# esp32.net
KiCad netlist of a schematic drawn in Altium Designer
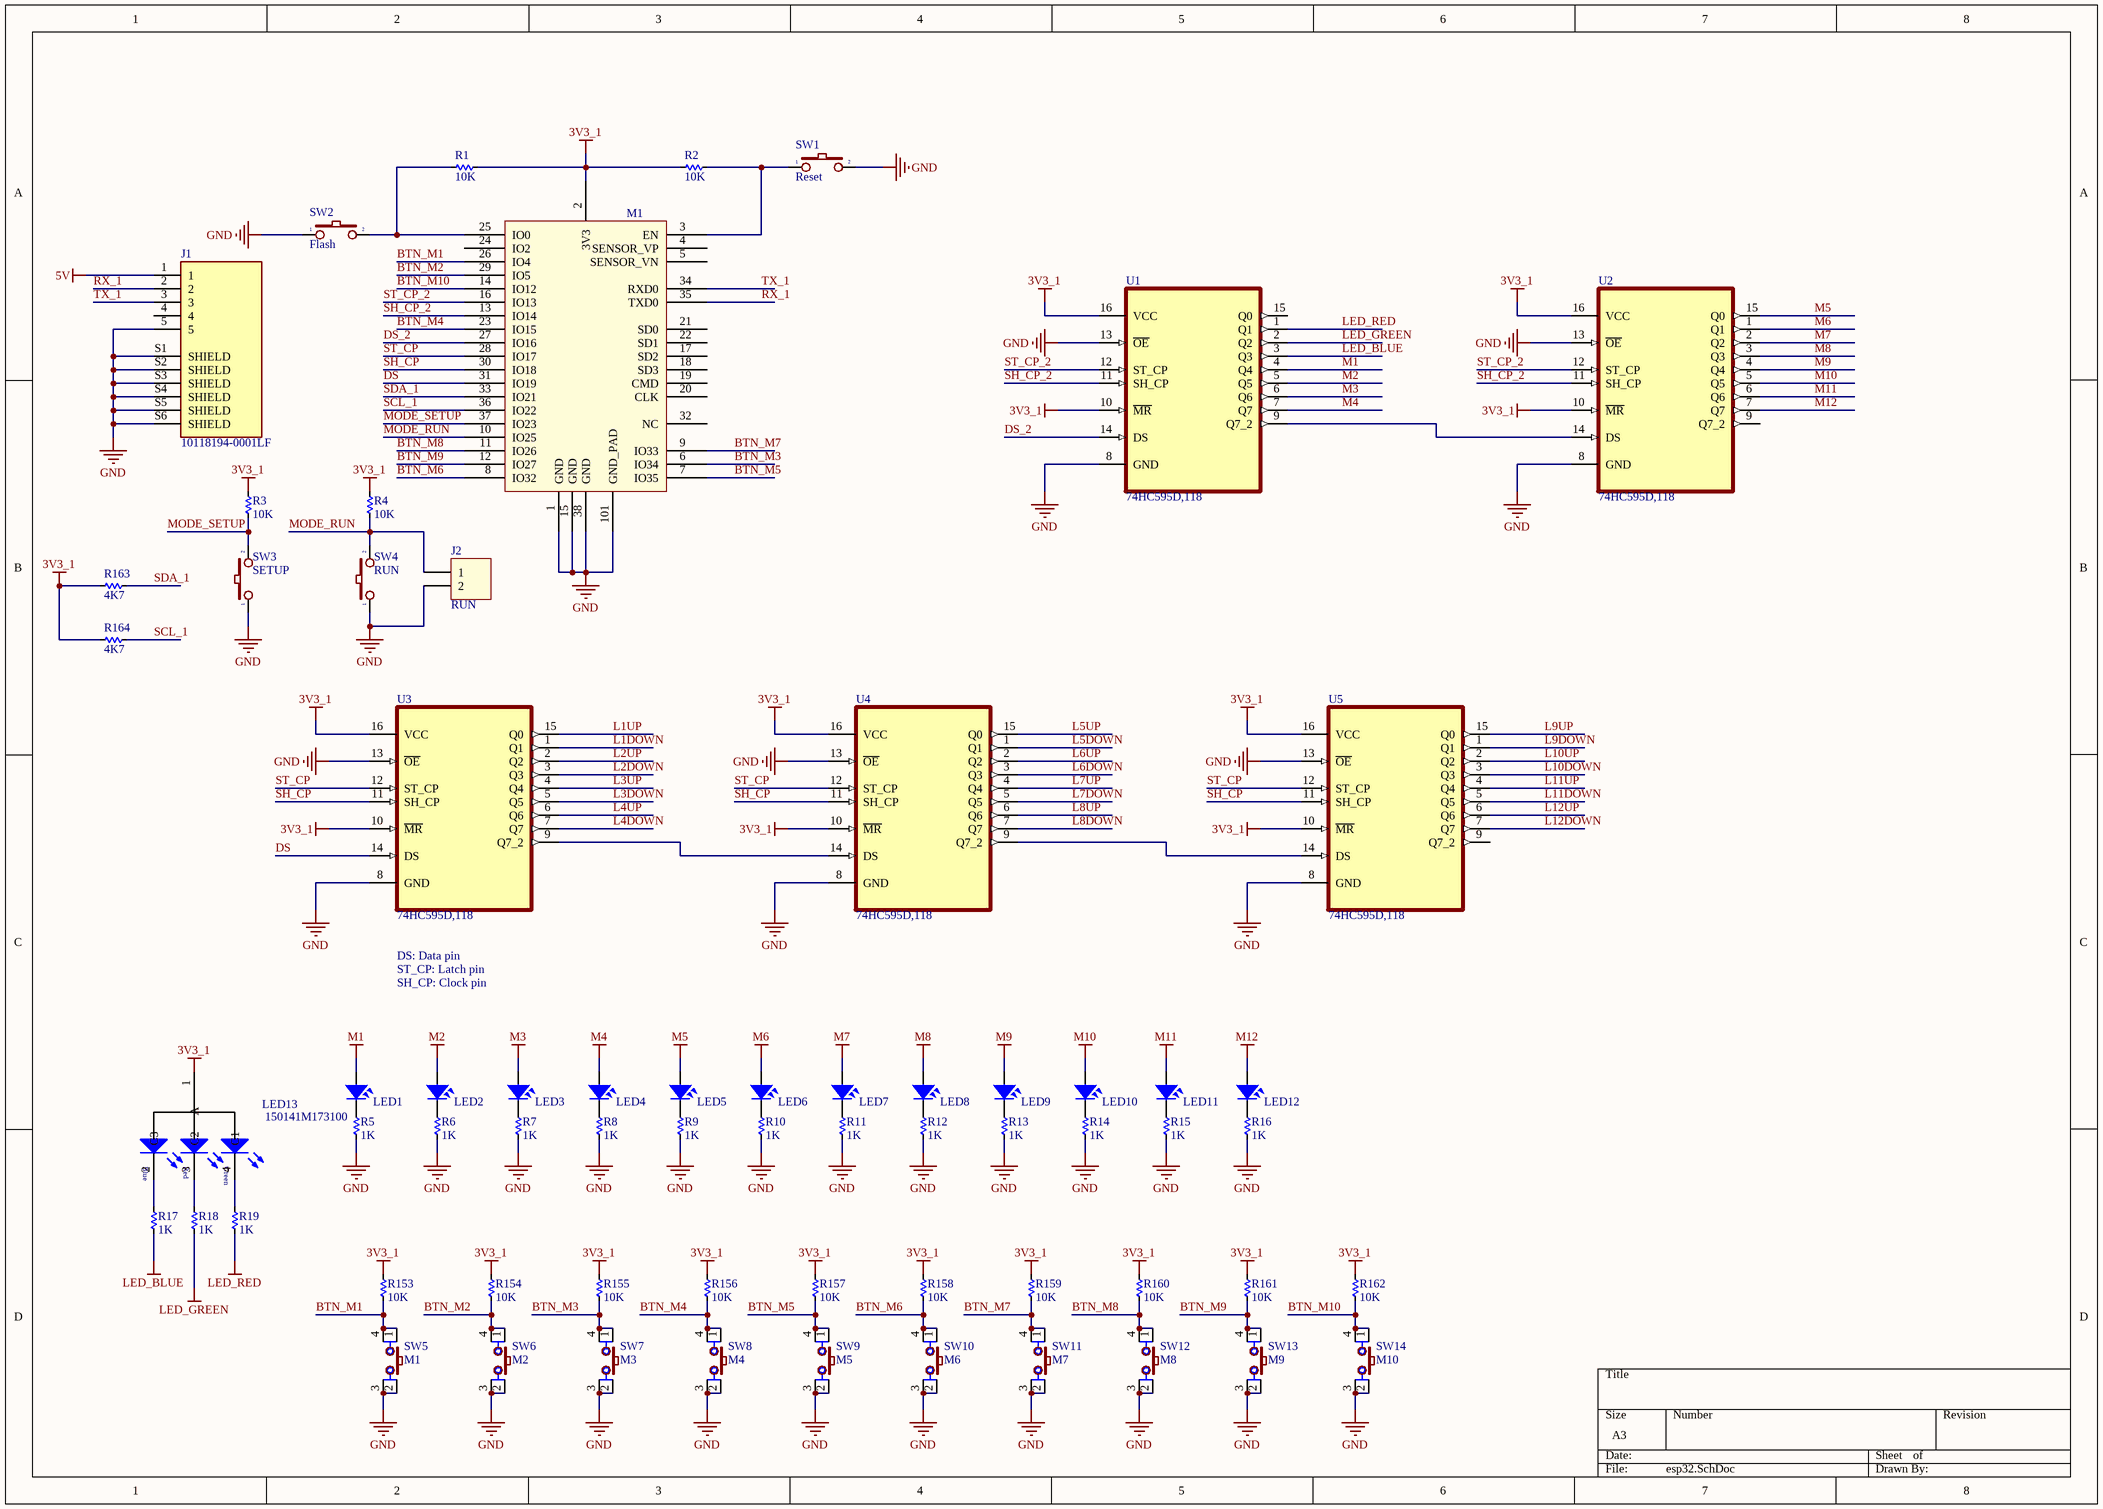
[diagram p0: esp32.SchDoc]

(export (version "E")
  (design (tool "Eeschema 10.0.6"))
  (components
    (comp (ref "J1")
      (value "10118194-0001LF")
      (footprint "AMPHENOL_10118194-0001LF")
      (description "USB - micro B USB 2.0 Receptacle Connector 5 Position Surface Mount, Right Angle; Through Hole")
      (fields (field (name "MF") "Amphenol ICC"))
      (libsource (lib "10118194-0001LF") (part "10118194-0001LF"))
    )
    (comp (ref "J2")
      (value "RUN")
      (footprint "62000211622")
      (description "WR-WTB 2.00mm Male Vertical Shrouded Header, 2p")
      (fields (field (name "PART NUMBER") "62000211622") (field (name "PUBLISHER") "Wurth Elektronik"))
      (libsource (lib "Header2.0") (part "62000211622"))
    )
    (comp (ref "LED1") (value "LED") (footprint "LED-0805-Blue") (libsource (lib "LIBRARY") (part "LED SMD")))
    (comp (ref "LED2") (value "LED") (footprint "LED-0805-Blue") (libsource (lib "LIBRARY") (part "LED SMD")))
    (comp (ref "LED3") (value "LED") (footprint "LED-0805-Blue") (libsource (lib "LIBRARY") (part "LED SMD")))
    (comp (ref "LED4") (value "LED") (footprint "LED-0805-Blue") (libsource (lib "LIBRARY") (part "LED SMD")))
    (comp (ref "LED5") (value "LED") (footprint "LED-0805-Blue") (libsource (lib "LIBRARY") (part "LED SMD")))
    (comp (ref "LED6") (value "LED") (footprint "LED-0805-Blue") (libsource (lib "LIBRARY") (part "LED SMD")))
    (comp (ref "LED7") (value "LED") (footprint "LED-0805-Blue") (libsource (lib "LIBRARY") (part "LED SMD")))
    (comp (ref "LED8") (value "LED") (footprint "LED-0805-Blue") (libsource (lib "LIBRARY") (part "LED SMD")))
    (comp (ref "LED9") (value "LED") (footprint "LED-0805-Blue") (libsource (lib "LIBRARY") (part "LED SMD")))
    (comp (ref "LED10")
      (value "LED")
      (footprint "LED-0805-Blue")
      (libsource (lib "LIBRARY") (part "LED SMD"))
    )
    (comp (ref "LED11")
      (value "LED")
      (footprint "LED-0805-Blue")
      (libsource (lib "LIBRARY") (part "LED SMD"))
    )
    (comp (ref "LED12")
      (value "LED")
      (footprint "LED-0805-Blue")
      (libsource (lib "LIBRARY") (part "LED SMD"))
    )
    (comp (ref "LED13")
      (value "150141M173100")
      (footprint "LED RGB 3528")
      (description "SMD Full-Color Top LED, WL-SFTW, Red & Green & Blue")
      (fields
        (field (name "MANUFACTURER") "Würth Elektronik eiSos GmbH")
        (field (name "CREATED BY") "Christin Otto")
      )
      (libsource (lib "LIBRARY") (part "LED RGB SMD"))
    )
    (comp (ref "M1")
      (value "ESP32S_Module")
      (footprint "ESP32S")
      (description "Esp-32S")
      (libsource (lib "ESP32S") (part "ESP32S_Module"))
    )
    (comp (ref "R1")
      (value "10K")
      (footprint "RES-SMD-0805")
      (description "Resistor")
      (fields
        (field (name "MANUFACTURER") "Generic Components")
        (field (name "PUBLISHER") "Altium Hobart Technology Centre")
      )
      (libsource (lib "LIBRARY") (part "Res-SMD"))
    )
    (comp (ref "R2")
      (value "10K")
      (footprint "RES-SMD-0805")
      (description "Resistor")
      (fields
        (field (name "MANUFACTURER") "Generic Components")
        (field (name "PUBLISHER") "Altium Hobart Technology Centre")
      )
      (libsource (lib "LIBRARY") (part "Res-SMD"))
    )
    (comp (ref "R3")
      (value "10K")
      (footprint "RES-SMD-0805")
      (description "Resistor")
      (fields
        (field (name "MANUFACTURER") "Generic Components")
        (field (name "PUBLISHER") "Altium Hobart Technology Centre")
      )
      (libsource (lib "LIBRARY") (part "Res-SMD"))
    )
    (comp (ref "R4")
      (value "10K")
      (footprint "RES-SMD-0805")
      (description "Resistor")
      (fields
        (field (name "MANUFACTURER") "Generic Components")
        (field (name "PUBLISHER") "Altium Hobart Technology Centre")
      )
      (libsource (lib "LIBRARY") (part "Res-SMD"))
    )
    (comp (ref "R5")
      (value "1K")
      (footprint "RES-SMD-0805")
      (description "Resistor")
      (fields
        (field (name "MANUFACTURER") "Generic Components")
        (field (name "PUBLISHER") "Altium Hobart Technology Centre")
      )
      (libsource (lib "LIBRARY") (part "Res-SMD"))
    )
    (comp (ref "R6")
      (value "1K")
      (footprint "RES-SMD-0805")
      (description "Resistor")
      (fields
        (field (name "MANUFACTURER") "Generic Components")
        (field (name "PUBLISHER") "Altium Hobart Technology Centre")
      )
      (libsource (lib "LIBRARY") (part "Res-SMD"))
    )
    (comp (ref "R7")
      (value "1K")
      (footprint "RES-SMD-0805")
      (description "Resistor")
      (fields
        (field (name "MANUFACTURER") "Generic Components")
        (field (name "PUBLISHER") "Altium Hobart Technology Centre")
      )
      (libsource (lib "LIBRARY") (part "Res-SMD"))
    )
    (comp (ref "R8")
      (value "1K")
      (footprint "RES-SMD-0805")
      (description "Resistor")
      (fields
        (field (name "MANUFACTURER") "Generic Components")
        (field (name "PUBLISHER") "Altium Hobart Technology Centre")
      )
      (libsource (lib "LIBRARY") (part "Res-SMD"))
    )
    (comp (ref "R9")
      (value "1K")
      (footprint "RES-SMD-0805")
      (description "Resistor")
      (fields
        (field (name "MANUFACTURER") "Generic Components")
        (field (name "PUBLISHER") "Altium Hobart Technology Centre")
      )
      (libsource (lib "LIBRARY") (part "Res-SMD"))
    )
    (comp (ref "R10")
      (value "1K")
      (footprint "RES-SMD-0805")
      (description "Resistor")
      (fields
        (field (name "MANUFACTURER") "Generic Components")
        (field (name "PUBLISHER") "Altium Hobart Technology Centre")
      )
      (libsource (lib "LIBRARY") (part "Res-SMD"))
    )
    (comp (ref "R11")
      (value "1K")
      (footprint "RES-SMD-0805")
      (description "Resistor")
      (fields
        (field (name "MANUFACTURER") "Generic Components")
        (field (name "PUBLISHER") "Altium Hobart Technology Centre")
      )
      (libsource (lib "LIBRARY") (part "Res-SMD"))
    )
    (comp (ref "R12")
      (value "1K")
      (footprint "RES-SMD-0805")
      (description "Resistor")
      (fields
        (field (name "MANUFACTURER") "Generic Components")
        (field (name "PUBLISHER") "Altium Hobart Technology Centre")
      )
      (libsource (lib "LIBRARY") (part "Res-SMD"))
    )
    (comp (ref "R13")
      (value "1K")
      (footprint "RES-SMD-0805")
      (description "Resistor")
      (fields
        (field (name "MANUFACTURER") "Generic Components")
        (field (name "PUBLISHER") "Altium Hobart Technology Centre")
      )
      (libsource (lib "LIBRARY") (part "Res-SMD"))
    )
    (comp (ref "R14")
      (value "1K")
      (footprint "RES-SMD-0805")
      (description "Resistor")
      (fields
        (field (name "MANUFACTURER") "Generic Components")
        (field (name "PUBLISHER") "Altium Hobart Technology Centre")
      )
      (libsource (lib "LIBRARY") (part "Res-SMD"))
    )
    (comp (ref "R15")
      (value "1K")
      (footprint "RES-SMD-0805")
      (description "Resistor")
      (fields
        (field (name "MANUFACTURER") "Generic Components")
        (field (name "PUBLISHER") "Altium Hobart Technology Centre")
      )
      (libsource (lib "LIBRARY") (part "Res-SMD"))
    )
    (comp (ref "R16")
      (value "1K")
      (footprint "RES-SMD-0805")
      (description "Resistor")
      (fields
        (field (name "MANUFACTURER") "Generic Components")
        (field (name "PUBLISHER") "Altium Hobart Technology Centre")
      )
      (libsource (lib "LIBRARY") (part "Res-SMD"))
    )
    (comp (ref "R17")
      (value "1K")
      (footprint "RES-SMD-0805")
      (description "Resistor")
      (fields
        (field (name "MANUFACTURER") "Generic Components")
        (field (name "PUBLISHER") "Altium Hobart Technology Centre")
      )
      (libsource (lib "LIBRARY") (part "Res-SMD"))
    )
    (comp (ref "R18")
      (value "1K")
      (footprint "RES-SMD-0805")
      (description "Resistor")
      (fields
        (field (name "MANUFACTURER") "Generic Components")
        (field (name "PUBLISHER") "Altium Hobart Technology Centre")
      )
      (libsource (lib "LIBRARY") (part "Res-SMD"))
    )
    (comp (ref "R19")
      (value "1K")
      (footprint "RES-SMD-0805")
      (description "Resistor")
      (fields
        (field (name "MANUFACTURER") "Generic Components")
        (field (name "PUBLISHER") "Altium Hobart Technology Centre")
      )
      (libsource (lib "LIBRARY") (part "Res-SMD"))
    )
    (comp (ref "R153")
      (value "10K")
      (footprint "RES-SMD-0805")
      (description "Resistor")
      (fields
        (field (name "MANUFACTURER") "Generic Components")
        (field (name "PUBLISHER") "Altium Hobart Technology Centre")
      )
      (libsource (lib "LIBRARY") (part "Res-SMD"))
    )
    (comp (ref "R154")
      (value "10K")
      (footprint "RES-SMD-0805")
      (description "Resistor")
      (fields
        (field (name "MANUFACTURER") "Generic Components")
        (field (name "PUBLISHER") "Altium Hobart Technology Centre")
      )
      (libsource (lib "LIBRARY") (part "Res-SMD"))
    )
    (comp (ref "R155")
      (value "10K")
      (footprint "RES-SMD-0805")
      (description "Resistor")
      (fields
        (field (name "MANUFACTURER") "Generic Components")
        (field (name "PUBLISHER") "Altium Hobart Technology Centre")
      )
      (libsource (lib "LIBRARY") (part "Res-SMD"))
    )
    (comp (ref "R156")
      (value "10K")
      (footprint "RES-SMD-0805")
      (description "Resistor")
      (fields
        (field (name "MANUFACTURER") "Generic Components")
        (field (name "PUBLISHER") "Altium Hobart Technology Centre")
      )
      (libsource (lib "LIBRARY") (part "Res-SMD"))
    )
    (comp (ref "R157")
      (value "10K")
      (footprint "RES-SMD-0805")
      (description "Resistor")
      (fields
        (field (name "MANUFACTURER") "Generic Components")
        (field (name "PUBLISHER") "Altium Hobart Technology Centre")
      )
      (libsource (lib "LIBRARY") (part "Res-SMD"))
    )
    (comp (ref "R158")
      (value "10K")
      (footprint "RES-SMD-0805")
      (description "Resistor")
      (fields
        (field (name "MANUFACTURER") "Generic Components")
        (field (name "PUBLISHER") "Altium Hobart Technology Centre")
      )
      (libsource (lib "LIBRARY") (part "Res-SMD"))
    )
    (comp (ref "R159")
      (value "10K")
      (footprint "RES-SMD-0805")
      (description "Resistor")
      (fields
        (field (name "MANUFACTURER") "Generic Components")
        (field (name "PUBLISHER") "Altium Hobart Technology Centre")
      )
      (libsource (lib "LIBRARY") (part "Res-SMD"))
    )
    (comp (ref "R160")
      (value "10K")
      (footprint "RES-SMD-0805")
      (description "Resistor")
      (fields
        (field (name "MANUFACTURER") "Generic Components")
        (field (name "PUBLISHER") "Altium Hobart Technology Centre")
      )
      (libsource (lib "LIBRARY") (part "Res-SMD"))
    )
    (comp (ref "R161")
      (value "10K")
      (footprint "RES-SMD-0805")
      (description "Resistor")
      (fields
        (field (name "MANUFACTURER") "Generic Components")
        (field (name "PUBLISHER") "Altium Hobart Technology Centre")
      )
      (libsource (lib "LIBRARY") (part "Res-SMD"))
    )
    (comp (ref "R162")
      (value "10K")
      (footprint "RES-SMD-0805")
      (description "Resistor")
      (fields
        (field (name "MANUFACTURER") "Generic Components")
        (field (name "PUBLISHER") "Altium Hobart Technology Centre")
      )
      (libsource (lib "LIBRARY") (part "Res-SMD"))
    )
    (comp (ref "R163")
      (value "4K7")
      (footprint "RES-SMD-0805")
      (description "Resistor")
      (fields
        (field (name "MANUFACTURER") "Generic Components")
        (field (name "PUBLISHER") "Altium Hobart Technology Centre")
      )
      (libsource (lib "LIBRARY") (part "Res-SMD"))
    )
    (comp (ref "R164")
      (value "4K7")
      (footprint "RES-SMD-0805")
      (description "Resistor")
      (fields
        (field (name "MANUFACTURER") "Generic Components")
        (field (name "PUBLISHER") "Altium Hobart Technology Centre")
      )
      (libsource (lib "LIBRARY") (part "Res-SMD"))
    )
    (comp (ref "SW1")
      (value "Reset")
      (footprint "SW1-SMD")
      (description "Switch button 2 pin")
      (libsource (lib "LIBRARY") (part "SW2"))
    )
    (comp (ref "SW2")
      (value "Flash")
      (footprint "SW-DIP1-1")
      (description "Switch button 2 pin")
      (libsource (lib "LIBRARY") (part "SW2"))
    )
    (comp (ref "SW3")
      (value "SETUP")
      (footprint "SW-DIP1-1")
      (description "Switch button 2 pin")
      (libsource (lib "LIBRARY") (part "SW2"))
    )
    (comp (ref "SW4")
      (value "RUN")
      (footprint "SW-DIP1-1")
      (description "Switch button 2 pin")
      (libsource (lib "LIBRARY") (part "SW2"))
    )
    (comp (ref "SW5")
      (value "M1")
      (footprint "SW2-SMD")
      (description "Switch button 4 pin")
      (libsource (lib "LIBTanCN") (part "SW4"))
    )
    (comp (ref "SW6")
      (value "M2")
      (footprint "SW2-SMD")
      (description "Switch button 4 pin")
      (libsource (lib "LIBTanCN") (part "SW4"))
    )
    (comp (ref "SW7")
      (value "M3")
      (footprint "SW2-SMD")
      (description "Switch button 4 pin")
      (libsource (lib "LIBTanCN") (part "SW4"))
    )
    (comp (ref "SW8")
      (value "M4")
      (footprint "SW2-SMD")
      (description "Switch button 4 pin")
      (libsource (lib "LIBTanCN") (part "SW4"))
    )
    (comp (ref "SW9")
      (value "M5")
      (footprint "SW2-SMD")
      (description "Switch button 4 pin")
      (libsource (lib "LIBTanCN") (part "SW4"))
    )
    (comp (ref "SW10")
      (value "M6")
      (footprint "SW2-SMD")
      (description "Switch button 4 pin")
      (libsource (lib "LIBTanCN") (part "SW4"))
    )
    (comp (ref "SW11")
      (value "M7")
      (footprint "SW2-SMD")
      (description "Switch button 4 pin")
      (libsource (lib "LIBTanCN") (part "SW4"))
    )
    (comp (ref "SW12")
      (value "M8")
      (footprint "SW2-SMD")
      (description "Switch button 4 pin")
      (libsource (lib "LIBTanCN") (part "SW4"))
    )
    (comp (ref "SW13")
      (value "M9")
      (footprint "SW2-SMD")
      (description "Switch button 4 pin")
      (libsource (lib "LIBTanCN") (part "SW4"))
    )
    (comp (ref "SW14")
      (value "M10")
      (footprint "SW2-SMD")
      (description "Switch button 4 pin")
      (libsource (lib "LIBTanCN") (part "SW4"))
    )
    (comp (ref "U1")
      (value "74HC595D,118")
      (footprint "SOIC127P600X175-16N")
      (description "Shift Shift Register 1 Element 8 Bit 16-SO")
      (fields (field (name "MF") "Nexperia USA Inc."))
      (libsource (lib "74HC595D_118") (part "74HC595D,118"))
    )
    (comp (ref "U2")
      (value "74HC595D,118")
      (footprint "SOIC127P600X175-16N")
      (description "Shift Shift Register 1 Element 8 Bit 16-SO")
      (fields (field (name "MF") "Nexperia USA Inc."))
      (libsource (lib "74HC595D_118") (part "74HC595D,118"))
    )
    (comp (ref "U3")
      (value "74HC595D,118")
      (footprint "SOIC127P600X175-16N")
      (description "Shift Shift Register 1 Element 8 Bit 16-SO")
      (fields (field (name "MF") "Nexperia USA Inc."))
      (libsource (lib "74HC595D_118") (part "74HC595D,118"))
    )
    (comp (ref "U4")
      (value "74HC595D,118")
      (footprint "SOIC127P600X175-16N")
      (description "Shift Shift Register 1 Element 8 Bit 16-SO")
      (fields (field (name "MF") "Nexperia USA Inc."))
      (libsource (lib "74HC595D_118") (part "74HC595D,118"))
    )
    (comp (ref "U5")
      (value "74HC595D,118")
      (footprint "SOIC127P600X175-16N")
      (description "Shift Shift Register 1 Element 8 Bit 16-SO")
      (fields (field (name "MF") "Nexperia USA Inc."))
      (libsource (lib "74HC595D_118") (part "74HC595D,118"))
    )
  )
  (nets
    (net (code "1") (name "/BTN_M1") (class "Default")
      (node (ref "M1") (pin "26") (pinfunction "IO4_26") (pintype "passive"))
      (node (ref "R153") (pin "2") (pinfunction "2_2") (pintype "passive"))
      (node (ref "SW5") (pin "1") (pintype "passive"))
      (node (ref "SW5") (pin "4") (pinfunction "4_4") (pintype "passive"))
    )
    (net (code "2") (name "/BTN_M2") (class "Default")
      (node (ref "M1") (pin "29") (pinfunction "IO5_29") (pintype "passive"))
      (node (ref "R154") (pin "2") (pinfunction "2_2") (pintype "passive"))
      (node (ref "SW6") (pin "1") (pintype "passive"))
      (node (ref "SW6") (pin "4") (pinfunction "4_4") (pintype "passive"))
    )
    (net (code "3") (name "/BTN_M3") (class "Default")
      (node (ref "M1") (pin "6") (pinfunction "IO34_6") (pintype "passive"))
      (node (ref "R155") (pin "2") (pinfunction "2_2") (pintype "passive"))
      (node (ref "SW7") (pin "1") (pintype "passive"))
      (node (ref "SW7") (pin "4") (pinfunction "4_4") (pintype "passive"))
    )
    (net (code "4") (name "/BTN_M4") (class "Default")
      (node (ref "M1") (pin "23") (pinfunction "IO15_23") (pintype "passive"))
      (node (ref "R156") (pin "2") (pinfunction "2_2") (pintype "passive"))
      (node (ref "SW8") (pin "1") (pintype "passive"))
      (node (ref "SW8") (pin "4") (pinfunction "4_4") (pintype "passive"))
    )
    (net (code "5") (name "/BTN_M5") (class "Default")
      (node (ref "M1") (pin "7") (pinfunction "IO35_7") (pintype "passive"))
      (node (ref "R157") (pin "2") (pinfunction "2_2") (pintype "passive"))
      (node (ref "SW9") (pin "1") (pintype "passive"))
      (node (ref "SW9") (pin "4") (pinfunction "4_4") (pintype "passive"))
    )
    (net (code "6") (name "/BTN_M6") (class "Default")
      (node (ref "M1") (pin "8") (pinfunction "IO32_8") (pintype "passive"))
      (node (ref "R158") (pin "2") (pinfunction "2_2") (pintype "passive"))
      (node (ref "SW10") (pin "1") (pintype "passive"))
      (node (ref "SW10") (pin "4") (pinfunction "4_4") (pintype "passive"))
    )
    (net (code "7") (name "/BTN_M7") (class "Default")
      (node (ref "M1") (pin "9") (pinfunction "IO33_9") (pintype "passive"))
      (node (ref "R159") (pin "2") (pinfunction "2_2") (pintype "passive"))
      (node (ref "SW11") (pin "1") (pintype "passive"))
      (node (ref "SW11") (pin "4") (pinfunction "4_4") (pintype "passive"))
    )
    (net (code "8") (name "/BTN_M8") (class "Default")
      (node (ref "M1") (pin "11") (pinfunction "IO26_11") (pintype "passive"))
      (node (ref "R160") (pin "2") (pinfunction "2_2") (pintype "passive"))
      (node (ref "SW12") (pin "1") (pintype "passive"))
      (node (ref "SW12") (pin "4") (pinfunction "4_4") (pintype "passive"))
    )
    (net (code "9") (name "/BTN_M9") (class "Default")
      (node (ref "M1") (pin "12") (pinfunction "IO27_12") (pintype "passive"))
      (node (ref "R161") (pin "2") (pinfunction "2_2") (pintype "passive"))
      (node (ref "SW13") (pin "1") (pintype "passive"))
      (node (ref "SW13") (pin "4") (pinfunction "4_4") (pintype "passive"))
    )
    (net (code "10") (name "/BTN_M10") (class "Default")
      (node (ref "M1") (pin "14") (pinfunction "IO12_14") (pintype "passive"))
      (node (ref "R162") (pin "2") (pinfunction "2_2") (pintype "passive"))
      (node (ref "SW14") (pin "1") (pintype "passive"))
      (node (ref "SW14") (pin "4") (pinfunction "4_4") (pintype "passive"))
    )
    (net (code "11") (name "/DS") (class "Default")
      (node (ref "M1") (pin "31") (pinfunction "IO19_31") (pintype "passive"))
      (node (ref "U3") (pin "14") (pinfunction "DS_14") (pintype "input"))
    )
    (net (code "12") (name "/DS_2") (class "Default")
      (node (ref "M1") (pin "27") (pinfunction "IO16_27") (pintype "passive"))
      (node (ref "U1") (pin "14") (pinfunction "DS_14") (pintype "input"))
    )
    (net (code "13") (name "/L1DOWN") (class "Default")
      (node (ref "U3") (pin "1") (pinfunction "Q1_1") (pintype "output"))
    )
    (net (code "14") (name "/L1UP") (class "Default")
      (node (ref "U3") (pin "15") (pinfunction "Q0_15") (pintype "output"))
    )
    (net (code "15") (name "/L2DOWN") (class "Default")
      (node (ref "U3") (pin "3") (pinfunction "Q3_3") (pintype "output"))
    )
    (net (code "16") (name "/L2UP") (class "Default")
      (node (ref "U3") (pin "2") (pinfunction "Q2_2") (pintype "output"))
    )
    (net (code "17") (name "/L3DOWN") (class "Default")
      (node (ref "U3") (pin "5") (pinfunction "Q5_5") (pintype "output"))
    )
    (net (code "18") (name "/L3UP") (class "Default")
      (node (ref "U3") (pin "4") (pinfunction "Q4_4") (pintype "output"))
    )
    (net (code "19") (name "/L4DOWN") (class "Default")
      (node (ref "U3") (pin "7") (pinfunction "Q7_7") (pintype "output"))
    )
    (net (code "20") (name "/L4UP") (class "Default")
      (node (ref "U3") (pin "6") (pinfunction "Q6_6") (pintype "output"))
    )
    (net (code "21") (name "/L5DOWN") (class "Default")
      (node (ref "U4") (pin "1") (pinfunction "Q1_1") (pintype "output"))
    )
    (net (code "22") (name "/L5UP") (class "Default")
      (node (ref "U4") (pin "15") (pinfunction "Q0_15") (pintype "output"))
    )
    (net (code "23") (name "/L6DOWN") (class "Default")
      (node (ref "U4") (pin "3") (pinfunction "Q3_3") (pintype "output"))
    )
    (net (code "24") (name "/L6UP") (class "Default")
      (node (ref "U4") (pin "2") (pinfunction "Q2_2") (pintype "output"))
    )
    (net (code "25") (name "/L7DOWN") (class "Default")
      (node (ref "U4") (pin "5") (pinfunction "Q5_5") (pintype "output"))
    )
    (net (code "26") (name "/L7UP") (class "Default")
      (node (ref "U4") (pin "4") (pinfunction "Q4_4") (pintype "output"))
    )
    (net (code "27") (name "/L8DOWN") (class "Default")
      (node (ref "U4") (pin "7") (pinfunction "Q7_7") (pintype "output"))
    )
    (net (code "28") (name "/L8UP") (class "Default")
      (node (ref "U4") (pin "6") (pinfunction "Q6_6") (pintype "output"))
    )
    (net (code "29") (name "/L9DOWN") (class "Default")
      (node (ref "U5") (pin "1") (pinfunction "Q1_1") (pintype "output"))
    )
    (net (code "30") (name "/L9UP") (class "Default")
      (node (ref "U5") (pin "15") (pinfunction "Q0_15") (pintype "output"))
    )
    (net (code "31") (name "/L10DOWN") (class "Default")
      (node (ref "U5") (pin "3") (pinfunction "Q3_3") (pintype "output"))
    )
    (net (code "32") (name "/L10UP") (class "Default")
      (node (ref "U5") (pin "2") (pinfunction "Q2_2") (pintype "output"))
    )
    (net (code "33") (name "/L11DOWN") (class "Default")
      (node (ref "U5") (pin "5") (pinfunction "Q5_5") (pintype "output"))
    )
    (net (code "34") (name "/L11UP") (class "Default")
      (node (ref "U5") (pin "4") (pinfunction "Q4_4") (pintype "output"))
    )
    (net (code "35") (name "/L12DOWN") (class "Default")
      (node (ref "U5") (pin "7") (pinfunction "Q7_7") (pintype "output"))
    )
    (net (code "36") (name "/L12UP") (class "Default")
      (node (ref "U5") (pin "6") (pinfunction "Q6_6") (pintype "output"))
    )
    (net (code "37") (name "/MODE_RUN") (class "Default")
      (node (ref "J2") (pin "1") (pinfunction "1_1") (pintype "passive"))
      (node (ref "M1") (pin "10") (pinfunction "IO25_10") (pintype "passive"))
      (node (ref "R4") (pin "2") (pinfunction "2_2") (pintype "passive"))
      (node (ref "SW4") (pin "2") (pinfunction "2_2") (pintype "passive"))
    )
    (net (code "38") (name "/MODE_SETUP") (class "Default")
      (node (ref "M1") (pin "37") (pinfunction "IO23_37") (pintype "passive"))
      (node (ref "R3") (pin "2") (pinfunction "2_2") (pintype "passive"))
      (node (ref "SW3") (pin "2") (pinfunction "2_2") (pintype "passive"))
    )
    (net (code "39") (name "/RX_1") (class "Default")
      (node (ref "J1") (pin "2") (pinfunction "2_2") (pintype "passive"))
      (node (ref "M1") (pin "35") (pinfunction "TXD0_35") (pintype "passive"))
    )
    (net (code "40") (name "/SCL_1") (class "Default")
      (node (ref "M1") (pin "36") (pinfunction "IO22_36") (pintype "passive"))
      (node (ref "R164") (pin "2") (pinfunction "2_2") (pintype "passive"))
    )
    (net (code "41") (name "/SDA_1") (class "Default")
      (node (ref "M1") (pin "33") (pinfunction "IO21_33") (pintype "passive"))
      (node (ref "R163") (pin "2") (pinfunction "2_2") (pintype "passive"))
    )
    (net (code "42") (name "/SH_CP") (class "Default")
      (node (ref "M1") (pin "30") (pinfunction "IO18_30") (pintype "passive"))
      (node (ref "U3") (pin "11") (pinfunction "SH_CP_11") (pintype "input"))
      (node (ref "U4") (pin "11") (pinfunction "SH_CP_11") (pintype "input"))
      (node (ref "U5") (pin "11") (pinfunction "SH_CP_11") (pintype "input"))
    )
    (net (code "43") (name "/SH_CP_2") (class "Default")
      (node (ref "M1") (pin "13") (pinfunction "IO14_13") (pintype "passive"))
      (node (ref "U1") (pin "11") (pinfunction "SH_CP_11") (pintype "input"))
      (node (ref "U2") (pin "11") (pinfunction "SH_CP_11") (pintype "input"))
    )
    (net (code "44") (name "/ST_CP") (class "Default")
      (node (ref "M1") (pin "28") (pinfunction "IO17_28") (pintype "passive"))
      (node (ref "U3") (pin "12") (pinfunction "ST_CP_12") (pintype "input"))
      (node (ref "U4") (pin "12") (pinfunction "ST_CP_12") (pintype "input"))
      (node (ref "U5") (pin "12") (pinfunction "ST_CP_12") (pintype "input"))
    )
    (net (code "45") (name "/ST_CP_2") (class "Default")
      (node (ref "M1") (pin "16") (pinfunction "IO13_16") (pintype "passive"))
      (node (ref "U1") (pin "12") (pinfunction "ST_CP_12") (pintype "input"))
      (node (ref "U2") (pin "12") (pinfunction "ST_CP_12") (pintype "input"))
    )
    (net (code "46") (name "/TX_1") (class "Default")
      (node (ref "J1") (pin "3") (pinfunction "3_3") (pintype "passive"))
      (node (ref "M1") (pin "34") (pinfunction "RXD0_34") (pintype "passive"))
    )
    (net (code "47") (name "3V3_1") (class "Default")
      (node (ref "LED13") (pin "1") (pinfunction "A_1") (pintype "passive"))
      (node (ref "M1") (pin "2") (pinfunction "3V3_2") (pintype "power_in"))
      (node (ref "R1") (pin "1") (pinfunction "1_1") (pintype "passive"))
      (node (ref "R153") (pin "1") (pinfunction "1_1") (pintype "passive"))
      (node (ref "R154") (pin "1") (pinfunction "1_1") (pintype "passive"))
      (node (ref "R155") (pin "1") (pinfunction "1_1") (pintype "passive"))
      (node (ref "R156") (pin "1") (pinfunction "1_1") (pintype "passive"))
      (node (ref "R157") (pin "1") (pinfunction "1_1") (pintype "passive"))
      (node (ref "R158") (pin "1") (pinfunction "1_1") (pintype "passive"))
      (node (ref "R159") (pin "1") (pinfunction "1_1") (pintype "passive"))
      (node (ref "R160") (pin "1") (pinfunction "1_1") (pintype "passive"))
      (node (ref "R161") (pin "1") (pinfunction "1_1") (pintype "passive"))
      (node (ref "R162") (pin "1") (pinfunction "1_1") (pintype "passive"))
      (node (ref "R163") (pin "1") (pinfunction "1_1") (pintype "passive"))
      (node (ref "R164") (pin "1") (pinfunction "1_1") (pintype "passive"))
      (node (ref "R2") (pin "2") (pinfunction "2_2") (pintype "passive"))
      (node (ref "R3") (pin "1") (pinfunction "1_1") (pintype "passive"))
      (node (ref "R4") (pin "1") (pinfunction "1_1") (pintype "passive"))
      (node (ref "U1") (pin "10") (pinfunction "~{MR}_10") (pintype "input"))
      (node (ref "U1") (pin "16") (pinfunction "VCC_16") (pintype "power_in"))
      (node (ref "U2") (pin "10") (pinfunction "~{MR}_10") (pintype "input"))
      (node (ref "U2") (pin "16") (pinfunction "VCC_16") (pintype "power_in"))
      (node (ref "U3") (pin "10") (pinfunction "~{MR}_10") (pintype "input"))
      (node (ref "U3") (pin "16") (pinfunction "VCC_16") (pintype "power_in"))
      (node (ref "U4") (pin "10") (pinfunction "~{MR}_10") (pintype "input"))
      (node (ref "U4") (pin "16") (pinfunction "VCC_16") (pintype "power_in"))
      (node (ref "U5") (pin "10") (pinfunction "~{MR}_10") (pintype "input"))
      (node (ref "U5") (pin "16") (pinfunction "VCC_16") (pintype "power_in"))
    )
    (net (code "48") (name "5V") (class "Default")
      (node (ref "J1") (pin "1") (pinfunction "1_1") (pintype "passive"))
    )
    (net (code "49") (name "GND") (class "Default")
      (node (ref "J1") (pin "5") (pinfunction "5_5") (pintype "passive"))
      (node (ref "J1") (pin "S1") (pinfunction "SHIELD_S1") (pintype "passive"))
      (node (ref "J1") (pin "S2") (pinfunction "SHIELD_S2") (pintype "passive"))
      (node (ref "J1") (pin "S3") (pinfunction "SHIELD_S3") (pintype "passive"))
      (node (ref "J1") (pin "S4") (pinfunction "SHIELD_S4") (pintype "passive"))
      (node (ref "J1") (pin "S5") (pinfunction "SHIELD_S5") (pintype "passive"))
      (node (ref "J1") (pin "S6") (pinfunction "SHIELD_S6") (pintype "passive"))
      (node (ref "J2") (pin "2") (pinfunction "2_2") (pintype "passive"))
      (node (ref "M1") (pin "1") (pinfunction "GND_1") (pintype "power_in"))
      (node (ref "M1") (pin "101") (pinfunction "GND_PAD_101") (pintype "power_in"))
      (node (ref "M1") (pin "15") (pinfunction "GND_15") (pintype "power_in"))
      (node (ref "M1") (pin "38") (pinfunction "GND_38") (pintype "power_in"))
      (node (ref "R10") (pin "2") (pinfunction "2_2") (pintype "passive"))
      (node (ref "R11") (pin "2") (pinfunction "2_2") (pintype "passive"))
      (node (ref "R12") (pin "2") (pinfunction "2_2") (pintype "passive"))
      (node (ref "R13") (pin "2") (pinfunction "2_2") (pintype "passive"))
      (node (ref "R14") (pin "2") (pinfunction "2_2") (pintype "passive"))
      (node (ref "R15") (pin "2") (pinfunction "2_2") (pintype "passive"))
      (node (ref "R16") (pin "2") (pinfunction "2_2") (pintype "passive"))
      (node (ref "R5") (pin "2") (pinfunction "2_2") (pintype "passive"))
      (node (ref "R6") (pin "2") (pinfunction "2_2") (pintype "passive"))
      (node (ref "R7") (pin "2") (pinfunction "2_2") (pintype "passive"))
      (node (ref "R8") (pin "2") (pinfunction "2_2") (pintype "passive"))
      (node (ref "R9") (pin "2") (pinfunction "2_2") (pintype "passive"))
      (node (ref "SW1") (pin "2") (pinfunction "2_2") (pintype "passive"))
      (node (ref "SW10") (pin "2") (pinfunction "2_2") (pintype "passive"))
      (node (ref "SW10") (pin "3") (pinfunction "3_3") (pintype "passive"))
      (node (ref "SW11") (pin "2") (pinfunction "2_2") (pintype "passive"))
      (node (ref "SW11") (pin "3") (pinfunction "3_3") (pintype "passive"))
      (node (ref "SW12") (pin "2") (pinfunction "2_2") (pintype "passive"))
      (node (ref "SW12") (pin "3") (pinfunction "3_3") (pintype "passive"))
      (node (ref "SW13") (pin "2") (pinfunction "2_2") (pintype "passive"))
      (node (ref "SW13") (pin "3") (pinfunction "3_3") (pintype "passive"))
      (node (ref "SW14") (pin "2") (pinfunction "2_2") (pintype "passive"))
      (node (ref "SW14") (pin "3") (pinfunction "3_3") (pintype "passive"))
      (node (ref "SW2") (pin "1") (pinfunction "1_1") (pintype "passive"))
      (node (ref "SW3") (pin "1") (pinfunction "1_1") (pintype "passive"))
      (node (ref "SW4") (pin "1") (pinfunction "1_1") (pintype "passive"))
      (node (ref "SW5") (pin "2") (pinfunction "2_2") (pintype "passive"))
      (node (ref "SW5") (pin "3") (pinfunction "3_3") (pintype "passive"))
      (node (ref "SW6") (pin "2") (pinfunction "2_2") (pintype "passive"))
      (node (ref "SW6") (pin "3") (pinfunction "3_3") (pintype "passive"))
      (node (ref "SW7") (pin "2") (pinfunction "2_2") (pintype "passive"))
      (node (ref "SW7") (pin "3") (pinfunction "3_3") (pintype "passive"))
      (node (ref "SW8") (pin "2") (pinfunction "2_2") (pintype "passive"))
      (node (ref "SW8") (pin "3") (pinfunction "3_3") (pintype "passive"))
      (node (ref "SW9") (pin "2") (pinfunction "2_2") (pintype "passive"))
      (node (ref "SW9") (pin "3") (pinfunction "3_3") (pintype "passive"))
      (node (ref "U1") (pin "13") (pinfunction "~{OE}_13") (pintype "input"))
      (node (ref "U1") (pin "8") (pinfunction "GND_8") (pintype "passive"))
      (node (ref "U2") (pin "13") (pinfunction "~{OE}_13") (pintype "input"))
      (node (ref "U2") (pin "8") (pinfunction "GND_8") (pintype "passive"))
      (node (ref "U3") (pin "13") (pinfunction "~{OE}_13") (pintype "input"))
      (node (ref "U3") (pin "8") (pinfunction "GND_8") (pintype "passive"))
      (node (ref "U4") (pin "13") (pinfunction "~{OE}_13") (pintype "input"))
      (node (ref "U4") (pin "8") (pinfunction "GND_8") (pintype "passive"))
      (node (ref "U5") (pin "13") (pinfunction "~{OE}_13") (pintype "input"))
      (node (ref "U5") (pin "8") (pinfunction "GND_8") (pintype "passive"))
    )
    (net (code "50") (name "LED_BLUE") (class "Default")
      (node (ref "R17") (pin "2") (pinfunction "2_2") (pintype "passive"))
      (node (ref "U1") (pin "3") (pinfunction "Q3_3") (pintype "output"))
    )
    (net (code "51") (name "LED_GREEN") (class "Default")
      (node (ref "R18") (pin "2") (pinfunction "2_2") (pintype "passive"))
      (node (ref "U1") (pin "2") (pinfunction "Q2_2") (pintype "output"))
    )
    (net (code "52") (name "LED_RED") (class "Default")
      (node (ref "R19") (pin "2") (pinfunction "2_2") (pintype "passive"))
      (node (ref "U1") (pin "1") (pinfunction "Q1_1") (pintype "output"))
    )
    (net (code "53") (name "M1") (class "Default")
      (node (ref "LED1") (pin "1") (pinfunction "1_1") (pintype "passive"))
      (node (ref "U1") (pin "4") (pinfunction "Q4_4") (pintype "output"))
    )
    (net (code "54") (name "M2") (class "Default")
      (node (ref "LED2") (pin "1") (pinfunction "1_1") (pintype "passive"))
      (node (ref "U1") (pin "5") (pinfunction "Q5_5") (pintype "output"))
    )
    (net (code "55") (name "M3") (class "Default")
      (node (ref "LED3") (pin "1") (pinfunction "1_1") (pintype "passive"))
      (node (ref "U1") (pin "6") (pinfunction "Q6_6") (pintype "output"))
    )
    (net (code "56") (name "M4") (class "Default")
      (node (ref "LED4") (pin "1") (pinfunction "1_1") (pintype "passive"))
      (node (ref "U1") (pin "7") (pinfunction "Q7_7") (pintype "output"))
    )
    (net (code "57") (name "M5") (class "Default")
      (node (ref "LED5") (pin "1") (pinfunction "1_1") (pintype "passive"))
      (node (ref "U2") (pin "15") (pinfunction "Q0_15") (pintype "output"))
    )
    (net (code "58") (name "M6") (class "Default")
      (node (ref "LED6") (pin "1") (pinfunction "1_1") (pintype "passive"))
      (node (ref "U2") (pin "1") (pinfunction "Q1_1") (pintype "output"))
    )
    (net (code "59") (name "M7") (class "Default")
      (node (ref "LED7") (pin "1") (pinfunction "1_1") (pintype "passive"))
      (node (ref "U2") (pin "2") (pinfunction "Q2_2") (pintype "output"))
    )
    (net (code "60") (name "M8") (class "Default")
      (node (ref "LED8") (pin "1") (pinfunction "1_1") (pintype "passive"))
      (node (ref "U2") (pin "3") (pinfunction "Q3_3") (pintype "output"))
    )
    (net (code "61") (name "M9") (class "Default")
      (node (ref "LED9") (pin "1") (pinfunction "1_1") (pintype "passive"))
      (node (ref "U2") (pin "4") (pinfunction "Q4_4") (pintype "output"))
    )
    (net (code "62") (name "M10") (class "Default")
      (node (ref "LED10") (pin "1") (pinfunction "1_1") (pintype "passive"))
      (node (ref "U2") (pin "5") (pinfunction "Q5_5") (pintype "output"))
    )
    (net (code "63") (name "M11") (class "Default")
      (node (ref "LED11") (pin "1") (pinfunction "1_1") (pintype "passive"))
      (node (ref "U2") (pin "6") (pinfunction "Q6_6") (pintype "output"))
    )
    (net (code "64") (name "M12") (class "Default")
      (node (ref "LED12") (pin "1") (pinfunction "1_1") (pintype "passive"))
      (node (ref "U2") (pin "7") (pinfunction "Q7_7") (pintype "output"))
    )
    (net (code "65") (name "Net-(LED1-Pad2)") (class "Default")
      (node (ref "LED1") (pin "2") (pinfunction "2_2") (pintype "passive"))
      (node (ref "R5") (pin "1") (pinfunction "1_1") (pintype "passive"))
    )
    (net (code "66") (name "Net-(LED2-Pad2)") (class "Default")
      (node (ref "LED2") (pin "2") (pinfunction "2_2") (pintype "passive"))
      (node (ref "R6") (pin "1") (pinfunction "1_1") (pintype "passive"))
    )
    (net (code "67") (name "Net-(LED3-Pad2)") (class "Default")
      (node (ref "LED3") (pin "2") (pinfunction "2_2") (pintype "passive"))
      (node (ref "R7") (pin "1") (pinfunction "1_1") (pintype "passive"))
    )
    (net (code "68") (name "Net-(LED4-Pad2)") (class "Default")
      (node (ref "LED4") (pin "2") (pinfunction "2_2") (pintype "passive"))
      (node (ref "R8") (pin "1") (pinfunction "1_1") (pintype "passive"))
    )
    (net (code "69") (name "Net-(LED5-Pad2)") (class "Default")
      (node (ref "LED5") (pin "2") (pinfunction "2_2") (pintype "passive"))
      (node (ref "R9") (pin "1") (pinfunction "1_1") (pintype "passive"))
    )
    (net (code "70") (name "Net-(LED6-Pad2)") (class "Default")
      (node (ref "LED6") (pin "2") (pinfunction "2_2") (pintype "passive"))
      (node (ref "R10") (pin "1") (pinfunction "1_1") (pintype "passive"))
    )
    (net (code "71") (name "Net-(LED7-Pad2)") (class "Default")
      (node (ref "LED7") (pin "2") (pinfunction "2_2") (pintype "passive"))
      (node (ref "R11") (pin "1") (pinfunction "1_1") (pintype "passive"))
    )
    (net (code "72") (name "Net-(LED8-Pad2)") (class "Default")
      (node (ref "LED8") (pin "2") (pinfunction "2_2") (pintype "passive"))
      (node (ref "R12") (pin "1") (pinfunction "1_1") (pintype "passive"))
    )
    (net (code "73") (name "Net-(LED9-Pad2)") (class "Default")
      (node (ref "LED9") (pin "2") (pinfunction "2_2") (pintype "passive"))
      (node (ref "R13") (pin "1") (pinfunction "1_1") (pintype "passive"))
    )
    (net (code "74") (name "Net-(LED10-Pad2)") (class "Default")
      (node (ref "LED10") (pin "2") (pinfunction "2_2") (pintype "passive"))
      (node (ref "R14") (pin "1") (pinfunction "1_1") (pintype "passive"))
    )
    (net (code "75") (name "Net-(LED11-Pad2)") (class "Default")
      (node (ref "LED11") (pin "2") (pinfunction "2_2") (pintype "passive"))
      (node (ref "R15") (pin "1") (pinfunction "1_1") (pintype "passive"))
    )
    (net (code "76") (name "Net-(LED12-Pad2)") (class "Default")
      (node (ref "LED12") (pin "2") (pinfunction "2_2") (pintype "passive"))
      (node (ref "R16") (pin "1") (pinfunction "1_1") (pintype "passive"))
    )
    (net (code "77") (name "Net-(LED13-C1)") (class "Default")
      (node (ref "LED13") (pin "4") (pinfunction "C1_4") (pintype "passive"))
      (node (ref "R19") (pin "1") (pinfunction "1_1") (pintype "passive"))
    )
    (net (code "78") (name "Net-(LED13-C2)") (class "Default")
      (node (ref "LED13") (pin "3") (pinfunction "C2_3") (pintype "passive"))
      (node (ref "R18") (pin "1") (pinfunction "1_1") (pintype "passive"))
    )
    (net (code "79") (name "Net-(LED13-C3)") (class "Default")
      (node (ref "LED13") (pin "2") (pinfunction "C3_2") (pintype "passive"))
      (node (ref "R17") (pin "1") (pinfunction "1_1") (pintype "passive"))
    )
    (net (code "80") (name "Net-(M1-EN)") (class "Default")
      (node (ref "M1") (pin "3") (pinfunction "EN_3") (pintype "power_in"))
      (node (ref "R2") (pin "1") (pinfunction "1_1") (pintype "passive"))
      (node (ref "SW1") (pin "1") (pinfunction "1_1") (pintype "passive"))
    )
    (net (code "81") (name "Net-(M1-IO0)") (class "Default")
      (node (ref "M1") (pin "25") (pinfunction "IO0_25") (pintype "passive"))
      (node (ref "R1") (pin "2") (pinfunction "2_2") (pintype "passive"))
      (node (ref "SW2") (pin "2") (pinfunction "2_2") (pintype "passive"))
    )
    (net (code "82") (name "Net-(U1-Q7_2)") (class "Default")
      (node (ref "U1") (pin "9") (pinfunction "Q7_2_9") (pintype "output"))
      (node (ref "U2") (pin "14") (pinfunction "DS_14") (pintype "input"))
    )
    (net (code "83") (name "Net-(U3-Q7_2)") (class "Default")
      (node (ref "U3") (pin "9") (pinfunction "Q7_2_9") (pintype "output"))
      (node (ref "U4") (pin "14") (pinfunction "DS_14") (pintype "input"))
    )
    (net (code "84") (name "Net-(U4-Q7_2)") (class "Default")
      (node (ref "U4") (pin "9") (pinfunction "Q7_2_9") (pintype "output"))
      (node (ref "U5") (pin "14") (pinfunction "DS_14") (pintype "input"))
    )
    (net (code "85") (name "unconnected-(J1-Pad4)") (class "Default")
      (node (ref "J1") (pin "4") (pinfunction "4_4") (pintype "passive"))
    )
    (net (code "86") (name "unconnected-(M1-CLK-Pad20)") (class "Default")
      (node (ref "M1") (pin "20") (pinfunction "CLK_20") (pintype "passive"))
    )
    (net (code "87") (name "unconnected-(M1-CMD-Pad19)") (class "Default")
      (node (ref "M1") (pin "19") (pinfunction "CMD_19") (pintype "passive"))
    )
    (net (code "88") (name "unconnected-(M1-IO2-Pad24)") (class "Default")
      (node (ref "M1") (pin "24") (pinfunction "IO2_24") (pintype "passive"))
    )
    (net (code "89") (name "unconnected-(M1-NC-Pad32)") (class "Default")
      (node (ref "M1") (pin "32") (pinfunction "NC_32") (pintype "passive"))
    )
    (net (code "90") (name "unconnected-(M1-SD0-Pad21)") (class "Default")
      (node (ref "M1") (pin "21") (pinfunction "SD0_21") (pintype "passive"))
    )
    (net (code "91") (name "unconnected-(M1-SD1-Pad22)") (class "Default")
      (node (ref "M1") (pin "22") (pinfunction "SD1_22") (pintype "passive"))
    )
    (net (code "92") (name "unconnected-(M1-SD2-Pad17)") (class "Default")
      (node (ref "M1") (pin "17") (pinfunction "SD2_17") (pintype "passive"))
    )
    (net (code "93") (name "unconnected-(M1-SD3-Pad18)") (class "Default")
      (node (ref "M1") (pin "18") (pinfunction "SD3_18") (pintype "passive"))
    )
    (net (code "94") (name "unconnected-(M1-SENSOR_VN-Pad5)") (class "Default")
      (node (ref "M1") (pin "5") (pinfunction "SENSOR_VN_5") (pintype "passive"))
    )
    (net (code "95") (name "unconnected-(M1-SENSOR_VP-Pad4)") (class "Default")
      (node (ref "M1") (pin "4") (pinfunction "SENSOR_VP_4") (pintype "passive"))
    )
    (net (code "96") (name "unconnected-(U1-Q0-Pad15)") (class "Default")
      (node (ref "U1") (pin "15") (pinfunction "Q0_15") (pintype "output"))
    )
    (net (code "97") (name "unconnected-(U2-Q7_2-Pad9)") (class "Default")
      (node (ref "U2") (pin "9") (pinfunction "Q7_2_9") (pintype "output"))
    )
    (net (code "98") (name "unconnected-(U5-Q7_2-Pad9)") (class "Default")
      (node (ref "U5") (pin "9") (pinfunction "Q7_2_9") (pintype "output"))
    )
  )
)
